# W011B.net
KiCad netlist of a schematic drawn in EAGLE
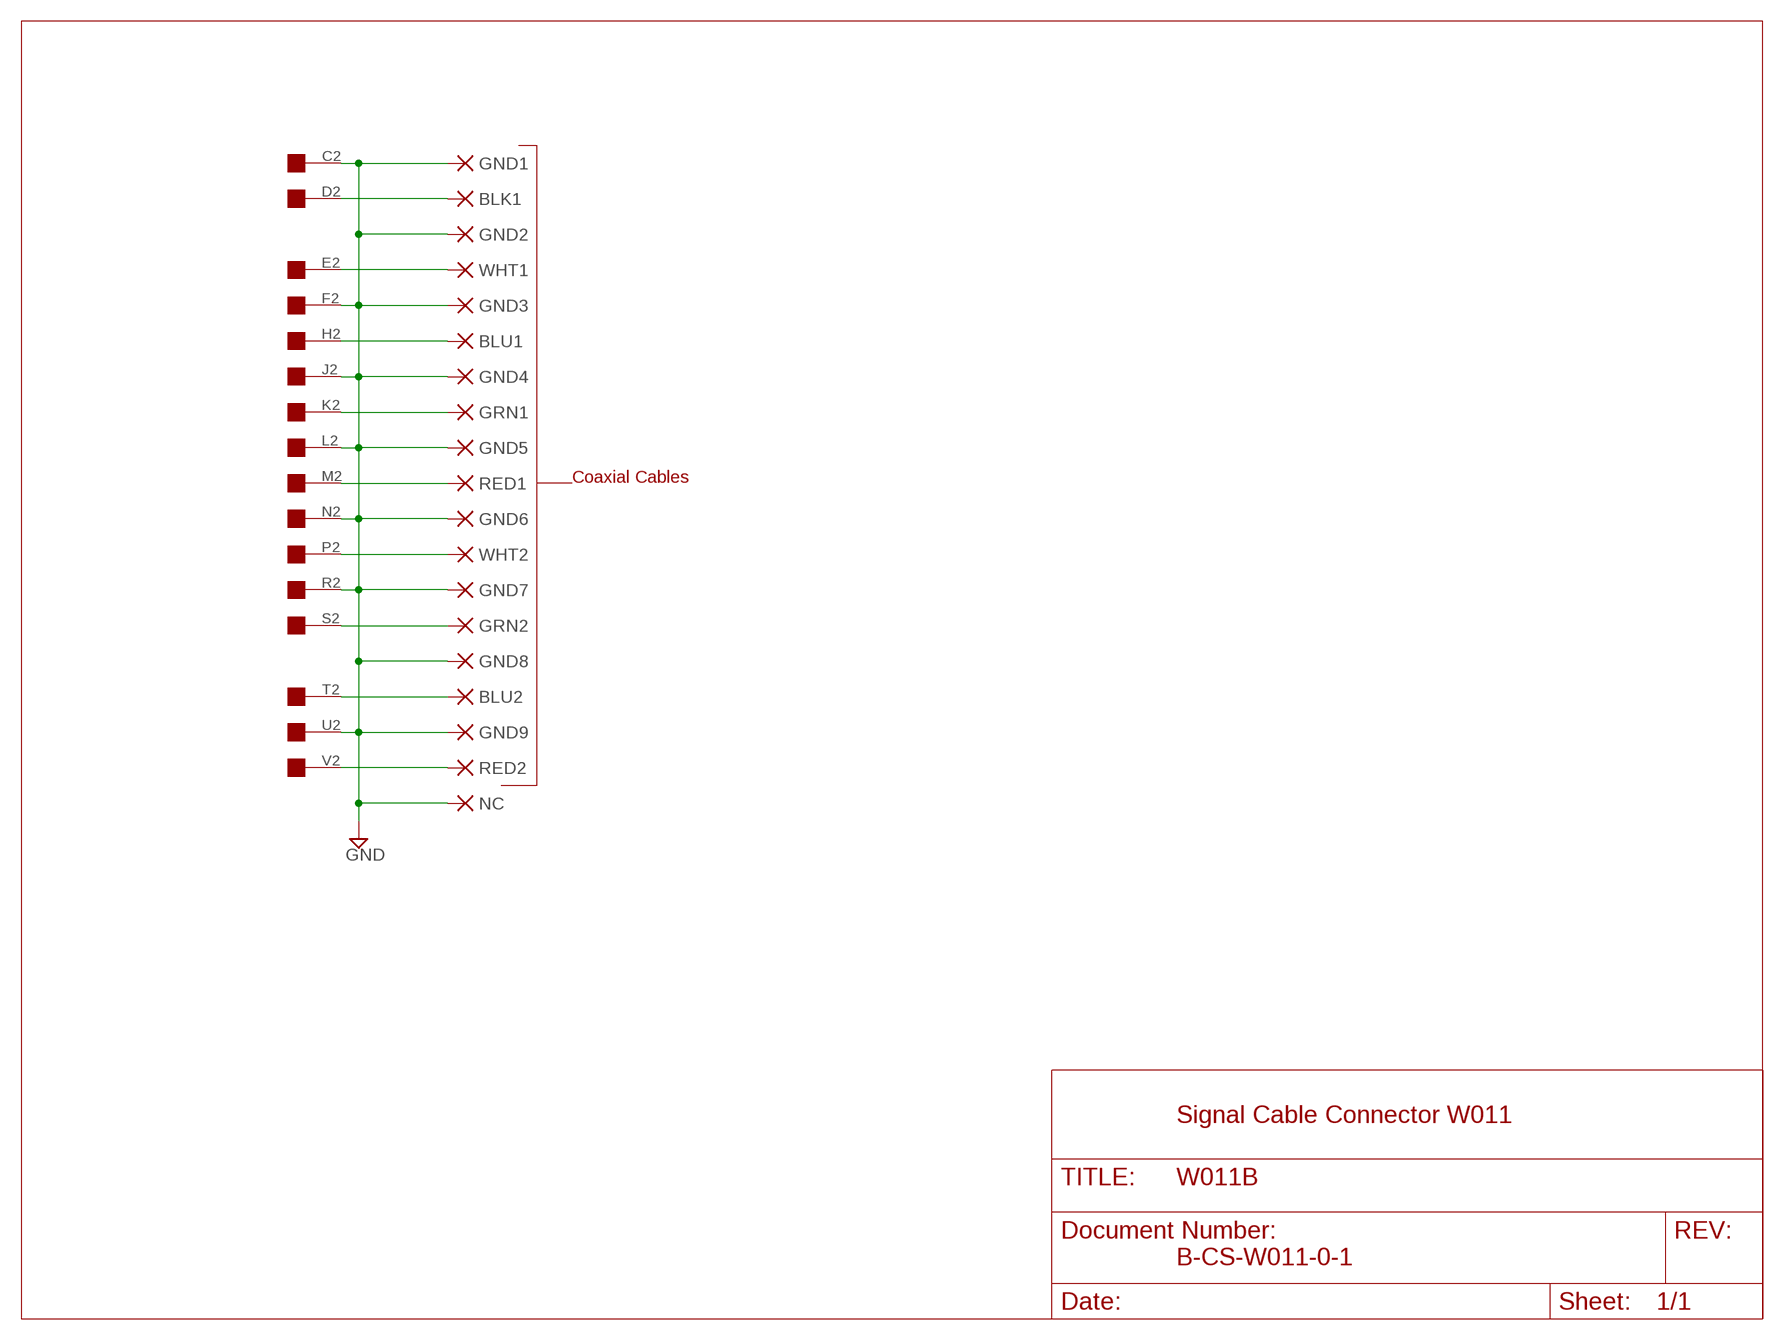
[diagram p0: schematic, sheet 1]

(export (version "E")
  (design (tool "Eeschema 10.0.6"))
  (components
    (comp (ref "BLK1")
      (value "PAD-0465")
      (footprint "eagle-import:0465")
      (libsource (lib "eagle-import") (part "PAD-0465"))
    )
    (comp (ref "BLU1")
      (value "PAD-0465")
      (footprint "eagle-import:0465")
      (libsource (lib "eagle-import") (part "PAD-0465"))
    )
    (comp (ref "BLU2")
      (value "PAD-0465")
      (footprint "eagle-import:0465")
      (libsource (lib "eagle-import") (part "PAD-0465"))
    )
    (comp (ref "GND1")
      (value "PAD-0465")
      (footprint "eagle-import:0465")
      (libsource (lib "eagle-import") (part "PAD-0465"))
    )
    (comp (ref "GND2")
      (value "PAD-0465")
      (footprint "eagle-import:0465")
      (libsource (lib "eagle-import") (part "PAD-0465"))
    )
    (comp (ref "GND3")
      (value "PAD-0465")
      (footprint "eagle-import:0465")
      (libsource (lib "eagle-import") (part "PAD-0465"))
    )
    (comp (ref "GND4")
      (value "PAD-0465")
      (footprint "eagle-import:0465")
      (libsource (lib "eagle-import") (part "PAD-0465"))
    )
    (comp (ref "GND5")
      (value "PAD-0465")
      (footprint "eagle-import:0465")
      (libsource (lib "eagle-import") (part "PAD-0465"))
    )
    (comp (ref "GND6")
      (value "PAD-0465")
      (footprint "eagle-import:0465")
      (libsource (lib "eagle-import") (part "PAD-0465"))
    )
    (comp (ref "GND7")
      (value "PAD-0465")
      (footprint "eagle-import:0465")
      (libsource (lib "eagle-import") (part "PAD-0465"))
    )
    (comp (ref "GND8")
      (value "PAD-0465")
      (footprint "eagle-import:0465")
      (libsource (lib "eagle-import") (part "PAD-0465"))
    )
    (comp (ref "GND9")
      (value "PAD-0465")
      (footprint "eagle-import:0465")
      (libsource (lib "eagle-import") (part "PAD-0465"))
    )
    (comp (ref "GRN1")
      (value "PAD-0465")
      (footprint "eagle-import:0465")
      (libsource (lib "eagle-import") (part "PAD-0465"))
    )
    (comp (ref "GRN2")
      (value "PAD-0465")
      (footprint "eagle-import:0465")
      (libsource (lib "eagle-import") (part "PAD-0465"))
    )
    (comp (ref "NC")
      (value "PAD-0465")
      (footprint "eagle-import:0465")
      (libsource (lib "eagle-import") (part "PAD-0465"))
    )
    (comp (ref "RED1")
      (value "PAD-0465")
      (footprint "eagle-import:0465")
      (libsource (lib "eagle-import") (part "PAD-0465"))
    )
    (comp (ref "RED2")
      (value "PAD-0465")
      (footprint "eagle-import:0465")
      (libsource (lib "eagle-import") (part "PAD-0465"))
    )
    (comp (ref "U$2")
      (value "EDGE-1")
      (footprint "eagle-import:EDGE-CON1")
      (libsource (lib "eagle-import") (part "EDGE-1"))
    )
    (comp (ref "WHT1")
      (value "PAD-0465")
      (footprint "eagle-import:0465")
      (libsource (lib "eagle-import") (part "PAD-0465"))
    )
    (comp (ref "WHT2")
      (value "PAD-0465")
      (footprint "eagle-import:0465")
      (libsource (lib "eagle-import") (part "PAD-0465"))
    )
  )
  (nets
    (net (code "1") (name "GND") (class "Default")
      (node (ref "GND1") (pin "P$1") (pinfunction "P_P$1") (pintype "passive"))
      (node (ref "GND2") (pin "P$1") (pinfunction "P_P$1") (pintype "passive"))
      (node (ref "GND3") (pin "P$1") (pinfunction "P_P$1") (pintype "passive"))
      (node (ref "GND4") (pin "P$1") (pinfunction "P_P$1") (pintype "passive"))
      (node (ref "GND5") (pin "P$1") (pinfunction "P_P$1") (pintype "passive"))
      (node (ref "GND6") (pin "P$1") (pinfunction "P_P$1") (pintype "passive"))
      (node (ref "GND7") (pin "P$1") (pinfunction "P_P$1") (pintype "passive"))
      (node (ref "GND8") (pin "P$1") (pinfunction "P_P$1") (pintype "passive"))
      (node (ref "GND9") (pin "P$1") (pinfunction "P_P$1") (pintype "passive"))
      (node (ref "NC") (pin "P$1") (pinfunction "P_P$1") (pintype "passive"))
      (node (ref "U$2") (pin "C2") (pinfunction "1_C2") (pintype "bidirectional"))
      (node (ref "U$2") (pin "F2") (pinfunction "1_F2") (pintype "bidirectional"))
      (node (ref "U$2") (pin "J2") (pinfunction "1_J2") (pintype "bidirectional"))
      (node (ref "U$2") (pin "L2") (pinfunction "1_L2") (pintype "bidirectional"))
      (node (ref "U$2") (pin "N2") (pinfunction "1_N2") (pintype "bidirectional"))
      (node (ref "U$2") (pin "R2") (pinfunction "1_R2") (pintype "bidirectional"))
      (node (ref "U$2") (pin "U2") (pinfunction "1_U2") (pintype "bidirectional"))
    )
    (net (code "2") (name "Net-(BLK1-P)") (class "Default")
      (node (ref "BLK1") (pin "P$1") (pinfunction "P_P$1") (pintype "passive"))
      (node (ref "U$2") (pin "D2") (pinfunction "1_D2") (pintype "bidirectional"))
    )
    (net (code "3") (name "Net-(BLU1-P)") (class "Default")
      (node (ref "BLU1") (pin "P$1") (pinfunction "P_P$1") (pintype "passive"))
      (node (ref "U$2") (pin "H2") (pinfunction "1_H2") (pintype "bidirectional"))
    )
    (net (code "4") (name "Net-(BLU2-P)") (class "Default")
      (node (ref "BLU2") (pin "P$1") (pinfunction "P_P$1") (pintype "passive"))
      (node (ref "U$2") (pin "T2") (pinfunction "1_T2") (pintype "bidirectional"))
    )
    (net (code "5") (name "Net-(GRN1-P)") (class "Default")
      (node (ref "GRN1") (pin "P$1") (pinfunction "P_P$1") (pintype "passive"))
      (node (ref "U$2") (pin "K2") (pinfunction "1_K2") (pintype "bidirectional"))
    )
    (net (code "6") (name "Net-(GRN2-P)") (class "Default")
      (node (ref "GRN2") (pin "P$1") (pinfunction "P_P$1") (pintype "passive"))
      (node (ref "U$2") (pin "S2") (pinfunction "1_S2") (pintype "bidirectional"))
    )
    (net (code "7") (name "Net-(RED1-P)") (class "Default")
      (node (ref "RED1") (pin "P$1") (pinfunction "P_P$1") (pintype "passive"))
      (node (ref "U$2") (pin "M2") (pinfunction "1_M2") (pintype "bidirectional"))
    )
    (net (code "8") (name "Net-(RED2-P)") (class "Default")
      (node (ref "RED2") (pin "P$1") (pinfunction "P_P$1") (pintype "passive"))
      (node (ref "U$2") (pin "V2") (pinfunction "1_V2") (pintype "bidirectional"))
    )
    (net (code "9") (name "Net-(U$2E-1)") (class "Default")
      (node (ref "U$2") (pin "E2") (pinfunction "1_E2") (pintype "bidirectional"))
      (node (ref "WHT1") (pin "P$1") (pinfunction "P_P$1") (pintype "passive"))
    )
    (net (code "10") (name "Net-(U$2M-1)") (class "Default")
      (node (ref "U$2") (pin "P2") (pinfunction "1_P2") (pintype "bidirectional"))
      (node (ref "WHT2") (pin "P$1") (pinfunction "P_P$1") (pintype "passive"))
    )
  )
)
